# SMI_Link_7-12.net
KiCad netlist of a schematic drawn in Altium Designer
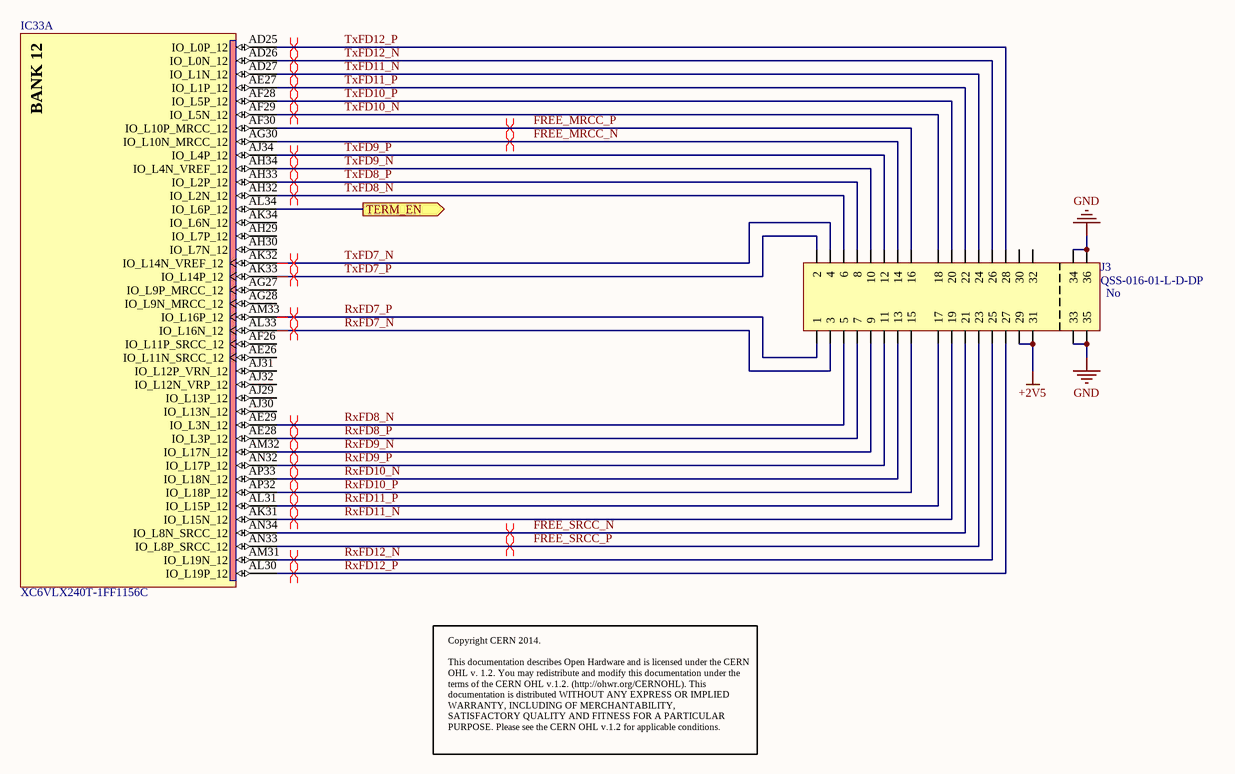
[diagram p0: SMI_Link_7-12.SchDoc]

(export (version "E")
  (design (tool "Eeschema 10.0.6"))
  (components
    (comp (ref "IC33")
      (value "XC6VLX240T-1FF1156C")
      (footprint "FF1156")
      (fields (field (name "PUBLISHER") "Altium Limited"))
      (libsource (lib "Xilinx Virtex-6") (part "XC6VLX240T-1FF1156C"))
    )
    (comp (ref "J3")
      (value "QSS-016-01-L-D-DP")
      (footprint "QSS-016-01-X-D-DP-A")
      (fields (field (name "MOUNTED") "No"))
      (libsource (lib "wr_switch") (part "QSS-016-01-L-D-DP"))
    )
  )
  (nets
    (net (code "1") (name "+2V5") (class "Default")
      (node (ref "J3") (pin "29") (pinfunction "29_29") (pintype "passive"))
      (node (ref "J3") (pin "31") (pinfunction "31_31") (pintype "passive"))
    )
    (net (code "2") (name "/FREE_MRCC_N") (class "Default")
      (node (ref "IC33") (pin "AG30") (pinfunction "IO_L10N_MRCC_12_AG30") (pintype "bidirectional"))
      (node (ref "J3") (pin "14") (pinfunction "14_14") (pintype "passive"))
    )
    (net (code "3") (name "/FREE_MRCC_P") (class "Default")
      (node (ref "IC33") (pin "AF30") (pinfunction "IO_L10P_MRCC_12_AF30") (pintype "bidirectional"))
      (node (ref "J3") (pin "16") (pinfunction "16_16") (pintype "passive"))
    )
    (net (code "4") (name "/FREE_SRCC_N") (class "Default")
      (node (ref "IC33") (pin "AN34") (pinfunction "IO_L8N_SRCC_12_AN34") (pintype "bidirectional"))
      (node (ref "J3") (pin "21") (pinfunction "21_21") (pintype "passive"))
    )
    (net (code "5") (name "/FREE_SRCC_P") (class "Default")
      (node (ref "IC33") (pin "AN33") (pinfunction "IO_L8P_SRCC_12_AN33") (pintype "bidirectional"))
      (node (ref "J3") (pin "23") (pinfunction "23_23") (pintype "passive"))
    )
    (net (code "6") (name "/RxFD7_N") (class "Default")
      (node (ref "IC33") (pin "AL33") (pinfunction "IO_L16N_12_AL33") (pintype "bidirectional"))
      (node (ref "J3") (pin "3") (pinfunction "3_3") (pintype "passive"))
    )
    (net (code "7") (name "/RxFD7_P") (class "Default")
      (node (ref "IC33") (pin "AM33") (pinfunction "IO_L16P_12_AM33") (pintype "bidirectional"))
      (node (ref "J3") (pin "1") (pinfunction "1_1") (pintype "passive"))
    )
    (net (code "8") (name "/RxFD8_N") (class "Default")
      (node (ref "IC33") (pin "AE29") (pinfunction "IO_L3N_12_AE29") (pintype "bidirectional"))
      (node (ref "J3") (pin "5") (pinfunction "5_5") (pintype "passive"))
    )
    (net (code "9") (name "/RxFD8_P") (class "Default")
      (node (ref "IC33") (pin "AE28") (pinfunction "IO_L3P_12_AE28") (pintype "bidirectional"))
      (node (ref "J3") (pin "7") (pinfunction "7_7") (pintype "passive"))
    )
    (net (code "10") (name "/RxFD9_N") (class "Default")
      (node (ref "IC33") (pin "AM32") (pinfunction "IO_L17N_12_AM32") (pintype "bidirectional"))
      (node (ref "J3") (pin "9") (pinfunction "9_9") (pintype "passive"))
    )
    (net (code "11") (name "/RxFD9_P") (class "Default")
      (node (ref "IC33") (pin "AN32") (pinfunction "IO_L17P_12_AN32") (pintype "bidirectional"))
      (node (ref "J3") (pin "11") (pinfunction "11_11") (pintype "passive"))
    )
    (net (code "12") (name "/RxFD10_N") (class "Default")
      (node (ref "IC33") (pin "AP33") (pinfunction "IO_L18N_12_AP33") (pintype "bidirectional"))
      (node (ref "J3") (pin "13") (pinfunction "13_13") (pintype "passive"))
    )
    (net (code "13") (name "/RxFD10_P") (class "Default")
      (node (ref "IC33") (pin "AP32") (pinfunction "IO_L18P_12_AP32") (pintype "bidirectional"))
      (node (ref "J3") (pin "15") (pinfunction "15_15") (pintype "passive"))
    )
    (net (code "14") (name "/RxFD11_N") (class "Default")
      (node (ref "IC33") (pin "AK31") (pinfunction "IO_L15N_12_AK31") (pintype "bidirectional"))
      (node (ref "J3") (pin "19") (pinfunction "19_19") (pintype "passive"))
    )
    (net (code "15") (name "/RxFD11_P") (class "Default")
      (node (ref "IC33") (pin "AL31") (pinfunction "IO_L15P_12_AL31") (pintype "bidirectional"))
      (node (ref "J3") (pin "17") (pinfunction "17_17") (pintype "passive"))
    )
    (net (code "16") (name "/RxFD12_N") (class "Default")
      (node (ref "IC33") (pin "AM31") (pinfunction "IO_L19N_12_AM31") (pintype "bidirectional"))
      (node (ref "J3") (pin "25") (pinfunction "25_25") (pintype "passive"))
    )
    (net (code "17") (name "/RxFD12_P") (class "Default")
      (node (ref "IC33") (pin "AL30") (pinfunction "IO_L19P_12_AL30") (pintype "bidirectional"))
      (node (ref "J3") (pin "27") (pinfunction "27_27") (pintype "passive"))
    )
    (net (code "18") (name "/TERM_EN") (class "Default")
      (node (ref "IC33") (pin "AL34") (pinfunction "IO_L6P_12_AL34") (pintype "bidirectional"))
    )
    (net (code "19") (name "/TxFD7_N") (class "Default")
      (node (ref "IC33") (pin "AK32") (pinfunction "IO_L14N_VREF_12_AK32") (pintype "bidirectional"))
      (node (ref "J3") (pin "4") (pinfunction "4_4") (pintype "passive"))
    )
    (net (code "20") (name "/TxFD7_P") (class "Default")
      (node (ref "IC33") (pin "AK33") (pinfunction "IO_L14P_12_AK33") (pintype "bidirectional"))
      (node (ref "J3") (pin "2") (pinfunction "2_2") (pintype "passive"))
    )
    (net (code "21") (name "/TxFD8_N") (class "Default")
      (node (ref "IC33") (pin "AH32") (pinfunction "IO_L2N_12_AH32") (pintype "bidirectional"))
      (node (ref "J3") (pin "6") (pinfunction "6_6") (pintype "passive"))
    )
    (net (code "22") (name "/TxFD8_P") (class "Default")
      (node (ref "IC33") (pin "AH33") (pinfunction "IO_L2P_12_AH33") (pintype "bidirectional"))
      (node (ref "J3") (pin "8") (pinfunction "8_8") (pintype "passive"))
    )
    (net (code "23") (name "/TxFD9_N") (class "Default")
      (node (ref "IC33") (pin "AH34") (pinfunction "IO_L4N_VREF_12_AH34") (pintype "bidirectional"))
      (node (ref "J3") (pin "10") (pinfunction "10_10") (pintype "passive"))
    )
    (net (code "24") (name "/TxFD9_P") (class "Default")
      (node (ref "IC33") (pin "AJ34") (pinfunction "IO_L4P_12_AJ34") (pintype "bidirectional"))
      (node (ref "J3") (pin "12") (pinfunction "12_12") (pintype "passive"))
    )
    (net (code "25") (name "/TxFD10_N") (class "Default")
      (node (ref "IC33") (pin "AF29") (pinfunction "IO_L5N_12_AF29") (pintype "bidirectional"))
      (node (ref "J3") (pin "18") (pinfunction "18_18") (pintype "passive"))
    )
    (net (code "26") (name "/TxFD10_P") (class "Default")
      (node (ref "IC33") (pin "AF28") (pinfunction "IO_L5P_12_AF28") (pintype "bidirectional"))
      (node (ref "J3") (pin "20") (pinfunction "20_20") (pintype "passive"))
    )
    (net (code "27") (name "/TxFD11_N") (class "Default")
      (node (ref "IC33") (pin "AD27") (pinfunction "IO_L1N_12_AD27") (pintype "bidirectional"))
      (node (ref "J3") (pin "24") (pinfunction "24_24") (pintype "passive"))
    )
    (net (code "28") (name "/TxFD11_P") (class "Default")
      (node (ref "IC33") (pin "AE27") (pinfunction "IO_L1P_12_AE27") (pintype "bidirectional"))
      (node (ref "J3") (pin "22") (pinfunction "22_22") (pintype "passive"))
    )
    (net (code "29") (name "/TxFD12_N") (class "Default")
      (node (ref "IC33") (pin "AD26") (pinfunction "IO_L0N_12_AD26") (pintype "bidirectional"))
      (node (ref "J3") (pin "26") (pinfunction "26_26") (pintype "passive"))
    )
    (net (code "30") (name "/TxFD12_P") (class "Default")
      (node (ref "IC33") (pin "AD25") (pinfunction "IO_L0P_12_AD25") (pintype "bidirectional"))
      (node (ref "J3") (pin "28") (pinfunction "28_28") (pintype "passive"))
    )
    (net (code "31") (name "GND") (class "Default")
      (node (ref "J3") (pin "33") (pinfunction "33_33") (pintype "passive"))
      (node (ref "J3") (pin "34") (pinfunction "34_34") (pintype "passive"))
      (node (ref "J3") (pin "35") (pinfunction "35_35") (pintype "passive"))
      (node (ref "J3") (pin "36") (pinfunction "36_36") (pintype "passive"))
    )
    (net (code "32") (name "unconnected-(IC33A-IO_L6N_12-PadAK34)") (class "Default")
      (node (ref "IC33") (pin "AK34") (pinfunction "IO_L6N_12_AK34") (pintype "bidirectional"))
    )
    (net (code "33") (name "unconnected-(IC33A-IO_L7N_12-PadAH30)") (class "Default")
      (node (ref "IC33") (pin "AH30") (pinfunction "IO_L7N_12_AH30") (pintype "bidirectional"))
    )
    (net (code "34") (name "unconnected-(IC33A-IO_L7P_12-PadAH29)") (class "Default")
      (node (ref "IC33") (pin "AH29") (pinfunction "IO_L7P_12_AH29") (pintype "bidirectional"))
    )
    (net (code "35") (name "unconnected-(IC33A-IO_L9N_MRCC_12-PadAG28)") (class "Default")
      (node (ref "IC33") (pin "AG28") (pinfunction "IO_L9N_MRCC_12_AG28") (pintype "bidirectional"))
    )
    (net (code "36") (name "unconnected-(IC33A-IO_L9P_MRCC_12-PadAG27)") (class "Default")
      (node (ref "IC33") (pin "AG27") (pinfunction "IO_L9P_MRCC_12_AG27") (pintype "bidirectional"))
    )
    (net (code "37") (name "unconnected-(IC33A-IO_L11N_SRCC_12-PadAE26)") (class "Default")
      (node (ref "IC33") (pin "AE26") (pinfunction "IO_L11N_SRCC_12_AE26") (pintype "bidirectional"))
    )
    (net (code "38") (name "unconnected-(IC33A-IO_L11P_SRCC_12-PadAF26)") (class "Default")
      (node (ref "IC33") (pin "AF26") (pinfunction "IO_L11P_SRCC_12_AF26") (pintype "bidirectional"))
    )
    (net (code "39") (name "unconnected-(IC33A-IO_L12N_VRP_12-PadAJ32)") (class "Default")
      (node (ref "IC33") (pin "AJ32") (pinfunction "IO_L12N_VRP_12_AJ32") (pintype "bidirectional"))
    )
    (net (code "40") (name "unconnected-(IC33A-IO_L12P_VRN_12-PadAJ31)") (class "Default")
      (node (ref "IC33") (pin "AJ31") (pinfunction "IO_L12P_VRN_12_AJ31") (pintype "bidirectional"))
    )
    (net (code "41") (name "unconnected-(IC33A-IO_L13N_12-PadAJ30)") (class "Default")
      (node (ref "IC33") (pin "AJ30") (pinfunction "IO_L13N_12_AJ30") (pintype "bidirectional"))
    )
    (net (code "42") (name "unconnected-(IC33A-IO_L13P_12-PadAJ29)") (class "Default")
      (node (ref "IC33") (pin "AJ29") (pinfunction "IO_L13P_12_AJ29") (pintype "bidirectional"))
    )
    (net (code "43") (name "unconnected-(J3-Pad30)") (class "Default")
      (node (ref "J3") (pin "30") (pinfunction "30_30") (pintype "passive"))
    )
    (net (code "44") (name "unconnected-(J3-Pad32)") (class "Default")
      (node (ref "J3") (pin "32") (pinfunction "32_32") (pintype "passive"))
    )
  )
)
